# Crumb_Adapter_neu2V1_2.net
KiCad netlist of a schematic drawn in EAGLE
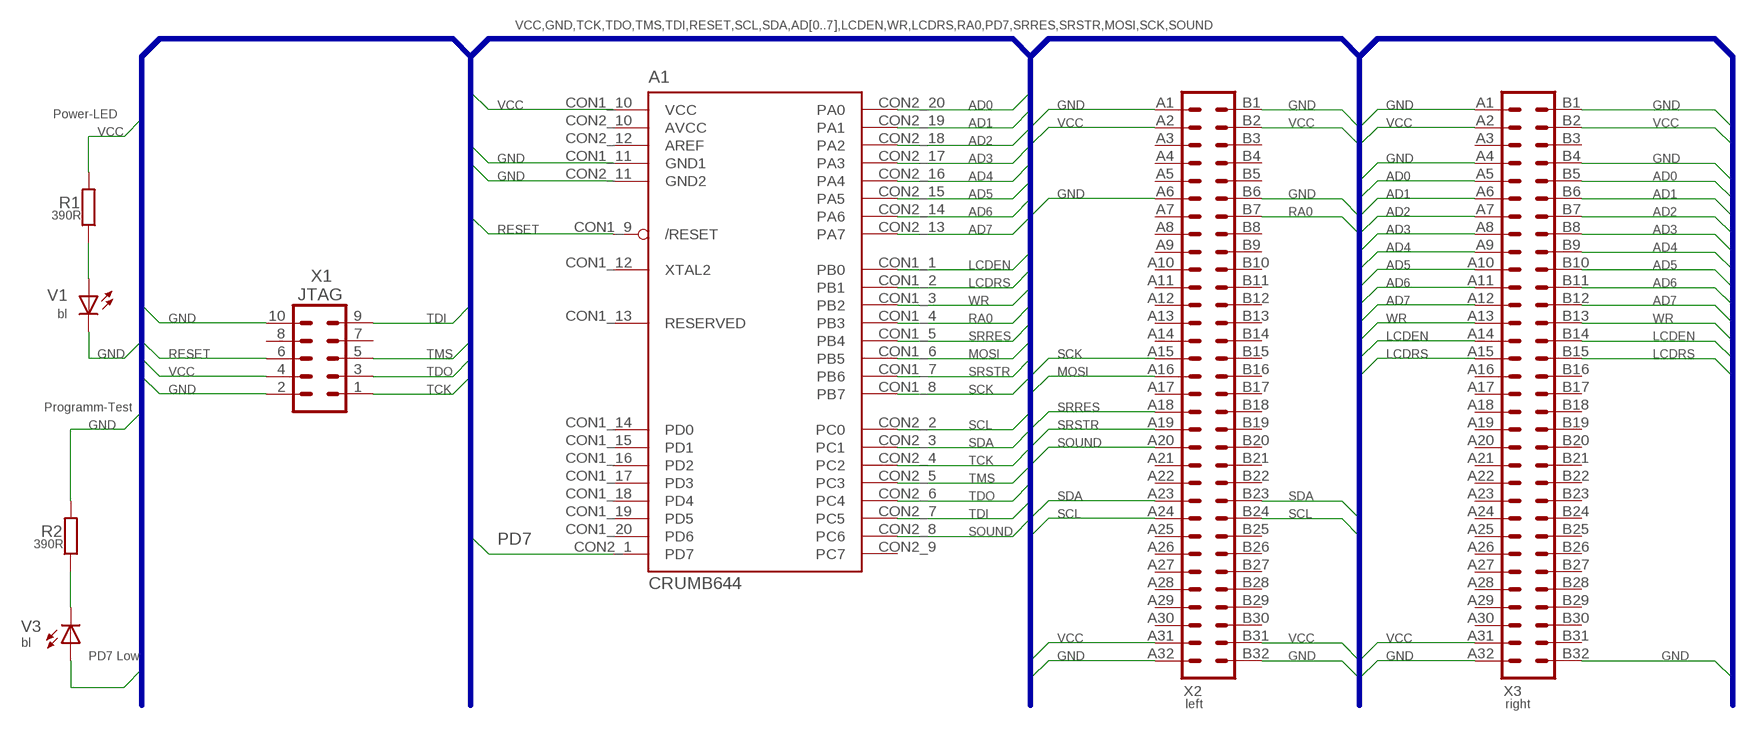
[diagram p0: schematic, sheet 1]

(export (version "E")
  (design (tool "Eeschema 10.0.6"))
  (components
    (comp (ref "A1")
      (value "CRUMB644")
      (footprint "eagle-import:CRUMB644")
      (libsource (lib "eagle-import") (part "CRUMB644"))
    )
    (comp (ref "R1")
      (value "390R")
      (footprint "eagle-import:M1206")
      (libsource (lib "eagle-import") (part "R-EU_VM1206"))
    )
    (comp (ref "R2")
      (value "390R")
      (footprint "eagle-import:M1206")
      (libsource (lib "eagle-import") (part "R-EU_VM1206"))
    )
    (comp (ref "V1")
      (value "bl")
      (footprint "eagle-import:CHIPLED_1206")
      (libsource (lib "eagle-import") (part "LEDCHIPLED_1206"))
    )
    (comp (ref "V3")
      (value "bl")
      (footprint "eagle-import:CHIPLED_1206")
      (libsource (lib "eagle-import") (part "LEDCHIPLED_1206"))
    )
    (comp (ref "X1")
      (value "JTAG")
      (footprint "eagle-import:MA05-2")
      (libsource (lib "eagle-import") (part "MA05-2"))
    )
    (comp (ref "X2")
      (value "left")
      (footprint "eagle-import:MAB32-2")
      (libsource (lib "eagle-import") (part "MAB64"))
    )
    (comp (ref "X3")
      (value "right")
      (footprint "eagle-import:MAB32-2")
      (libsource (lib "eagle-import") (part "MAB64"))
    )
  )
  (nets
    (net (code "1") (name "/AD0") (class "Default")
      (node (ref "A1") (pin "CON2_20") (pinfunction "PA0_CON2_20") (pintype "bidirectional"))
      (node (ref "X3") (pin "A5") (pinfunction "A5_A5") (pintype "passive"))
      (node (ref "X3") (pin "B5") (pinfunction "B5_B5") (pintype "passive"))
    )
    (net (code "2") (name "/AD1") (class "Default")
      (node (ref "A1") (pin "CON2_19") (pinfunction "PA1_CON2_19") (pintype "bidirectional"))
      (node (ref "X3") (pin "A6") (pinfunction "A6_A6") (pintype "passive"))
      (node (ref "X3") (pin "B6") (pinfunction "B6_B6") (pintype "passive"))
    )
    (net (code "3") (name "/AD2") (class "Default")
      (node (ref "A1") (pin "CON2_18") (pinfunction "PA2_CON2_18") (pintype "bidirectional"))
      (node (ref "X3") (pin "A7") (pinfunction "A7_A7") (pintype "passive"))
      (node (ref "X3") (pin "B7") (pinfunction "B7_B7") (pintype "passive"))
    )
    (net (code "4") (name "/AD3") (class "Default")
      (node (ref "A1") (pin "CON2_17") (pinfunction "PA3_CON2_17") (pintype "bidirectional"))
      (node (ref "X3") (pin "A8") (pinfunction "A8_A8") (pintype "passive"))
      (node (ref "X3") (pin "B8") (pinfunction "B8_B8") (pintype "passive"))
    )
    (net (code "5") (name "/AD4") (class "Default")
      (node (ref "A1") (pin "CON2_16") (pinfunction "PA4_CON2_16") (pintype "bidirectional"))
      (node (ref "X3") (pin "A9") (pinfunction "A9_A9") (pintype "passive"))
      (node (ref "X3") (pin "B9") (pinfunction "B9_B9") (pintype "passive"))
    )
    (net (code "6") (name "/AD5") (class "Default")
      (node (ref "A1") (pin "CON2_15") (pinfunction "PA5_CON2_15") (pintype "bidirectional"))
      (node (ref "X3") (pin "A10") (pinfunction "A10_A10") (pintype "passive"))
      (node (ref "X3") (pin "B10") (pinfunction "B10_B10") (pintype "passive"))
    )
    (net (code "7") (name "/AD6") (class "Default")
      (node (ref "A1") (pin "CON2_14") (pinfunction "PA6_CON2_14") (pintype "bidirectional"))
      (node (ref "X3") (pin "A11") (pinfunction "A11_A11") (pintype "passive"))
      (node (ref "X3") (pin "B11") (pinfunction "B11_B11") (pintype "passive"))
    )
    (net (code "8") (name "/AD7") (class "Default")
      (node (ref "A1") (pin "CON2_13") (pinfunction "PA7_CON2_13") (pintype "bidirectional"))
      (node (ref "X3") (pin "A12") (pinfunction "A12_A12") (pintype "passive"))
      (node (ref "X3") (pin "B12") (pinfunction "B12_B12") (pintype "passive"))
    )
    (net (code "9") (name "/GND") (class "Default")
      (node (ref "A1") (pin "CON1_11") (pinfunction "GND1_CON1_11") (pintype "power_in"))
      (node (ref "A1") (pin "CON2_11") (pinfunction "GND2_CON2_11") (pintype "power_in"))
      (node (ref "R2") (pin "2") (pinfunction "2_2") (pintype "passive"))
      (node (ref "V1") (pin "C") (pinfunction "C_C") (pintype "passive"))
      (node (ref "X1") (pin "10") (pinfunction "10_10") (pintype "passive"))
      (node (ref "X1") (pin "2") (pinfunction "2_2") (pintype "passive"))
      (node (ref "X2") (pin "A1") (pinfunction "A1_A1") (pintype "passive"))
      (node (ref "X2") (pin "A32") (pinfunction "A32_A32") (pintype "passive"))
      (node (ref "X2") (pin "A6") (pinfunction "A6_A6") (pintype "passive"))
      (node (ref "X2") (pin "B1") (pinfunction "B1_B1") (pintype "passive"))
      (node (ref "X2") (pin "B32") (pinfunction "B32_B32") (pintype "passive"))
      (node (ref "X2") (pin "B6") (pinfunction "B6_B6") (pintype "passive"))
      (node (ref "X3") (pin "A1") (pinfunction "A1_A1") (pintype "passive"))
      (node (ref "X3") (pin "A32") (pinfunction "A32_A32") (pintype "passive"))
      (node (ref "X3") (pin "A4") (pinfunction "A4_A4") (pintype "passive"))
      (node (ref "X3") (pin "B1") (pinfunction "B1_B1") (pintype "passive"))
      (node (ref "X3") (pin "B32") (pinfunction "B32_B32") (pintype "passive"))
      (node (ref "X3") (pin "B4") (pinfunction "B4_B4") (pintype "passive"))
    )
    (net (code "10") (name "/LCDEN") (class "Default")
      (node (ref "A1") (pin "CON1_1") (pinfunction "PB0_CON1_1") (pintype "bidirectional"))
      (node (ref "X3") (pin "A14") (pinfunction "A14_A14") (pintype "passive"))
      (node (ref "X3") (pin "B14") (pinfunction "B14_B14") (pintype "passive"))
    )
    (net (code "11") (name "/LCDRS") (class "Default")
      (node (ref "A1") (pin "CON1_2") (pinfunction "PB1_CON1_2") (pintype "bidirectional"))
      (node (ref "X3") (pin "A15") (pinfunction "A15_A15") (pintype "passive"))
      (node (ref "X3") (pin "B15") (pinfunction "B15_B15") (pintype "passive"))
    )
    (net (code "12") (name "/MOSI") (class "Default")
      (node (ref "A1") (pin "CON1_6") (pinfunction "PB5_CON1_6") (pintype "bidirectional"))
      (node (ref "X2") (pin "A16") (pinfunction "A16_A16") (pintype "passive"))
    )
    (net (code "13") (name "/PD7") (class "Default")
      (node (ref "A1") (pin "CON2_1") (pinfunction "PD7_CON2_1") (pintype "bidirectional"))
      (node (ref "V3") (pin "A") (pinfunction "A_A") (pintype "passive"))
    )
    (net (code "14") (name "/RA0") (class "Default")
      (node (ref "A1") (pin "CON1_4") (pinfunction "PB3_CON1_4") (pintype "bidirectional"))
      (node (ref "X2") (pin "B7") (pinfunction "B7_B7") (pintype "passive"))
    )
    (net (code "15") (name "/RESET") (class "Default")
      (node (ref "A1") (pin "CON1_9") (pinfunction "/RESET_CON1_9") (pintype "input"))
      (node (ref "X1") (pin "6") (pinfunction "6_6") (pintype "passive"))
    )
    (net (code "16") (name "/SCK") (class "Default")
      (node (ref "A1") (pin "CON1_8") (pinfunction "PB7_CON1_8") (pintype "bidirectional"))
      (node (ref "X2") (pin "A15") (pinfunction "A15_A15") (pintype "passive"))
    )
    (net (code "17") (name "/SCL") (class "Default")
      (node (ref "A1") (pin "CON2_2") (pinfunction "PC0_CON2_2") (pintype "bidirectional"))
      (node (ref "X2") (pin "A24") (pinfunction "A24_A24") (pintype "passive"))
      (node (ref "X2") (pin "B24") (pinfunction "B24_B24") (pintype "passive"))
    )
    (net (code "18") (name "/SDA") (class "Default")
      (node (ref "A1") (pin "CON2_3") (pinfunction "PC1_CON2_3") (pintype "bidirectional"))
      (node (ref "X2") (pin "A23") (pinfunction "A23_A23") (pintype "passive"))
      (node (ref "X2") (pin "B23") (pinfunction "B23_B23") (pintype "passive"))
    )
    (net (code "19") (name "/SOUND") (class "Default")
      (node (ref "A1") (pin "CON2_8") (pinfunction "PC6_CON2_8") (pintype "bidirectional"))
      (node (ref "X2") (pin "A20") (pinfunction "A20_A20") (pintype "passive"))
    )
    (net (code "20") (name "/SRRES") (class "Default")
      (node (ref "A1") (pin "CON1_5") (pinfunction "PB4_CON1_5") (pintype "bidirectional"))
      (node (ref "X2") (pin "A18") (pinfunction "A18_A18") (pintype "passive"))
    )
    (net (code "21") (name "/SRSTR") (class "Default")
      (node (ref "A1") (pin "CON1_7") (pinfunction "PB6_CON1_7") (pintype "bidirectional"))
      (node (ref "X2") (pin "A19") (pinfunction "A19_A19") (pintype "passive"))
    )
    (net (code "22") (name "/TCK") (class "Default")
      (node (ref "A1") (pin "CON2_4") (pinfunction "PC2_CON2_4") (pintype "bidirectional"))
      (node (ref "X1") (pin "1") (pinfunction "1_1") (pintype "passive"))
    )
    (net (code "23") (name "/TDI") (class "Default")
      (node (ref "A1") (pin "CON2_7") (pinfunction "PC5_CON2_7") (pintype "bidirectional"))
      (node (ref "X1") (pin "9") (pinfunction "9_9") (pintype "passive"))
    )
    (net (code "24") (name "/TDO") (class "Default")
      (node (ref "A1") (pin "CON2_6") (pinfunction "PC4_CON2_6") (pintype "bidirectional"))
      (node (ref "X1") (pin "3") (pinfunction "3_3") (pintype "passive"))
    )
    (net (code "25") (name "/TMS") (class "Default")
      (node (ref "A1") (pin "CON2_5") (pinfunction "PC3_CON2_5") (pintype "bidirectional"))
      (node (ref "X1") (pin "5") (pinfunction "5_5") (pintype "passive"))
    )
    (net (code "26") (name "/VCC") (class "Default")
      (node (ref "A1") (pin "CON1_10") (pinfunction "VCC_CON1_10") (pintype "power_in"))
      (node (ref "R1") (pin "2") (pinfunction "2_2") (pintype "passive"))
      (node (ref "X1") (pin "4") (pinfunction "4_4") (pintype "passive"))
      (node (ref "X2") (pin "A2") (pinfunction "A2_A2") (pintype "passive"))
      (node (ref "X2") (pin "A31") (pinfunction "A31_A31") (pintype "passive"))
      (node (ref "X2") (pin "B2") (pinfunction "B2_B2") (pintype "passive"))
      (node (ref "X2") (pin "B31") (pinfunction "B31_B31") (pintype "passive"))
      (node (ref "X3") (pin "A2") (pinfunction "A2_A2") (pintype "passive"))
      (node (ref "X3") (pin "A31") (pinfunction "A31_A31") (pintype "passive"))
      (node (ref "X3") (pin "B2") (pinfunction "B2_B2") (pintype "passive"))
    )
    (net (code "27") (name "/WR") (class "Default")
      (node (ref "A1") (pin "CON1_3") (pinfunction "PB2_CON1_3") (pintype "bidirectional"))
      (node (ref "X3") (pin "A13") (pinfunction "A13_A13") (pintype "passive"))
      (node (ref "X3") (pin "B13") (pinfunction "B13_B13") (pintype "passive"))
    )
    (net (code "29") (name "Net-(R1-Pad1)") (class "Default")
      (node (ref "R1") (pin "1") (pinfunction "1_1") (pintype "passive"))
      (node (ref "V1") (pin "A") (pinfunction "A_A") (pintype "passive"))
    )
    (net (code "30") (name "Net-(R2-Pad1)") (class "Default")
      (node (ref "R2") (pin "1") (pinfunction "1_1") (pintype "passive"))
      (node (ref "V3") (pin "C") (pinfunction "C_C") (pintype "passive"))
    )
    (net (code "31") (name "unconnected-(A1-AREF-PadCON2_12)") (class "Default")
      (node (ref "A1") (pin "CON2_12") (pinfunction "AREF_CON2_12") (pintype "input"))
    )
    (net (code "32") (name "unconnected-(A1-AVCC-PadCON2_10)") (class "Default")
      (node (ref "A1") (pin "CON2_10") (pinfunction "AVCC_CON2_10") (pintype "input"))
    )
    (net (code "33") (name "unconnected-(A1-PC7-PadCON2_9)") (class "Default")
      (node (ref "A1") (pin "CON2_9") (pinfunction "PC7_CON2_9") (pintype "bidirectional"))
    )
    (net (code "34") (name "unconnected-(A1-PD0-PadCON1_14)") (class "Default")
      (node (ref "A1") (pin "CON1_14") (pinfunction "PD0_CON1_14") (pintype "bidirectional"))
    )
    (net (code "35") (name "unconnected-(A1-PD1-PadCON1_15)") (class "Default")
      (node (ref "A1") (pin "CON1_15") (pinfunction "PD1_CON1_15") (pintype "bidirectional"))
    )
    (net (code "36") (name "unconnected-(A1-PD2-PadCON1_16)") (class "Default")
      (node (ref "A1") (pin "CON1_16") (pinfunction "PD2_CON1_16") (pintype "bidirectional"))
    )
    (net (code "37") (name "unconnected-(A1-PD3-PadCON1_17)") (class "Default")
      (node (ref "A1") (pin "CON1_17") (pinfunction "PD3_CON1_17") (pintype "bidirectional"))
    )
    (net (code "38") (name "unconnected-(A1-PD4-PadCON1_18)") (class "Default")
      (node (ref "A1") (pin "CON1_18") (pinfunction "PD4_CON1_18") (pintype "bidirectional"))
    )
    (net (code "39") (name "unconnected-(A1-PD5-PadCON1_19)") (class "Default")
      (node (ref "A1") (pin "CON1_19") (pinfunction "PD5_CON1_19") (pintype "bidirectional"))
    )
    (net (code "40") (name "unconnected-(A1-PD6-PadCON1_20)") (class "Default")
      (node (ref "A1") (pin "CON1_20") (pinfunction "PD6_CON1_20") (pintype "bidirectional"))
    )
    (net (code "41") (name "unconnected-(A1-RESERVED-PadCON1_13)") (class "Default")
      (node (ref "A1") (pin "CON1_13") (pinfunction "RESERVED_CON1_13") (pintype "no_connect"))
    )
    (net (code "42") (name "unconnected-(A1-XTAL2-PadCON1_12)") (class "Default")
      (node (ref "A1") (pin "CON1_12") (pinfunction "XTAL2_CON1_12") (pintype "bidirectional"))
    )
    (net (code "43") (name "unconnected-(X1-Pad7)") (class "Default")
      (node (ref "X1") (pin "7") (pinfunction "7_7") (pintype "passive"))
    )
    (net (code "44") (name "unconnected-(X1-Pad8)") (class "Default")
      (node (ref "X1") (pin "8") (pinfunction "8_8") (pintype "passive"))
    )
    (net (code "45") (name "unconnected-(X2-PadA3)") (class "Default")
      (node (ref "X2") (pin "A3") (pinfunction "A3_A3") (pintype "passive"))
    )
    (net (code "46") (name "unconnected-(X2-PadA4)") (class "Default")
      (node (ref "X2") (pin "A4") (pinfunction "A4_A4") (pintype "passive"))
    )
    (net (code "47") (name "unconnected-(X2-PadA5)") (class "Default")
      (node (ref "X2") (pin "A5") (pinfunction "A5_A5") (pintype "passive"))
    )
    (net (code "48") (name "unconnected-(X2-PadA7)") (class "Default")
      (node (ref "X2") (pin "A7") (pinfunction "A7_A7") (pintype "passive"))
    )
    (net (code "49") (name "unconnected-(X2-PadA8)") (class "Default")
      (node (ref "X2") (pin "A8") (pinfunction "A8_A8") (pintype "passive"))
    )
    (net (code "50") (name "unconnected-(X2-PadA9)") (class "Default")
      (node (ref "X2") (pin "A9") (pinfunction "A9_A9") (pintype "passive"))
    )
    (net (code "51") (name "unconnected-(X2-PadA10)") (class "Default")
      (node (ref "X2") (pin "A10") (pinfunction "A10_A10") (pintype "passive"))
    )
    (net (code "52") (name "unconnected-(X2-PadA11)") (class "Default")
      (node (ref "X2") (pin "A11") (pinfunction "A11_A11") (pintype "passive"))
    )
    (net (code "53") (name "unconnected-(X2-PadA12)") (class "Default")
      (node (ref "X2") (pin "A12") (pinfunction "A12_A12") (pintype "passive"))
    )
    (net (code "54") (name "unconnected-(X2-PadA13)") (class "Default")
      (node (ref "X2") (pin "A13") (pinfunction "A13_A13") (pintype "passive"))
    )
    (net (code "55") (name "unconnected-(X2-PadA14)") (class "Default")
      (node (ref "X2") (pin "A14") (pinfunction "A14_A14") (pintype "passive"))
    )
    (net (code "56") (name "unconnected-(X2-PadA17)") (class "Default")
      (node (ref "X2") (pin "A17") (pinfunction "A17_A17") (pintype "passive"))
    )
    (net (code "57") (name "unconnected-(X2-PadA21)") (class "Default")
      (node (ref "X2") (pin "A21") (pinfunction "A21_A21") (pintype "passive"))
    )
    (net (code "58") (name "unconnected-(X2-PadA22)") (class "Default")
      (node (ref "X2") (pin "A22") (pinfunction "A22_A22") (pintype "passive"))
    )
    (net (code "59") (name "unconnected-(X2-PadA25)") (class "Default")
      (node (ref "X2") (pin "A25") (pinfunction "A25_A25") (pintype "passive"))
    )
    (net (code "60") (name "unconnected-(X2-PadA26)") (class "Default")
      (node (ref "X2") (pin "A26") (pinfunction "A26_A26") (pintype "passive"))
    )
    (net (code "61") (name "unconnected-(X2-PadA27)") (class "Default")
      (node (ref "X2") (pin "A27") (pinfunction "A27_A27") (pintype "passive"))
    )
    (net (code "62") (name "unconnected-(X2-PadA28)") (class "Default")
      (node (ref "X2") (pin "A28") (pinfunction "A28_A28") (pintype "passive"))
    )
    (net (code "63") (name "unconnected-(X2-PadA29)") (class "Default")
      (node (ref "X2") (pin "A29") (pinfunction "A29_A29") (pintype "passive"))
    )
    (net (code "64") (name "unconnected-(X2-PadA30)") (class "Default")
      (node (ref "X2") (pin "A30") (pinfunction "A30_A30") (pintype "passive"))
    )
    (net (code "65") (name "unconnected-(X2-PadB3)") (class "Default")
      (node (ref "X2") (pin "B3") (pinfunction "B3_B3") (pintype "passive"))
    )
    (net (code "66") (name "unconnected-(X2-PadB4)") (class "Default")
      (node (ref "X2") (pin "B4") (pinfunction "B4_B4") (pintype "passive"))
    )
    (net (code "67") (name "unconnected-(X2-PadB5)") (class "Default")
      (node (ref "X2") (pin "B5") (pinfunction "B5_B5") (pintype "passive"))
    )
    (net (code "68") (name "unconnected-(X2-PadB8)") (class "Default")
      (node (ref "X2") (pin "B8") (pinfunction "B8_B8") (pintype "passive"))
    )
    (net (code "69") (name "unconnected-(X2-PadB9)") (class "Default")
      (node (ref "X2") (pin "B9") (pinfunction "B9_B9") (pintype "passive"))
    )
    (net (code "70") (name "unconnected-(X2-PadB10)") (class "Default")
      (node (ref "X2") (pin "B10") (pinfunction "B10_B10") (pintype "passive"))
    )
    (net (code "71") (name "unconnected-(X2-PadB11)") (class "Default")
      (node (ref "X2") (pin "B11") (pinfunction "B11_B11") (pintype "passive"))
    )
    (net (code "72") (name "unconnected-(X2-PadB12)") (class "Default")
      (node (ref "X2") (pin "B12") (pinfunction "B12_B12") (pintype "passive"))
    )
    (net (code "73") (name "unconnected-(X2-PadB13)") (class "Default")
      (node (ref "X2") (pin "B13") (pinfunction "B13_B13") (pintype "passive"))
    )
    (net (code "74") (name "unconnected-(X2-PadB14)") (class "Default")
      (node (ref "X2") (pin "B14") (pinfunction "B14_B14") (pintype "passive"))
    )
    (net (code "75") (name "unconnected-(X2-PadB15)") (class "Default")
      (node (ref "X2") (pin "B15") (pinfunction "B15_B15") (pintype "passive"))
    )
    (net (code "76") (name "unconnected-(X2-PadB16)") (class "Default")
      (node (ref "X2") (pin "B16") (pinfunction "B16_B16") (pintype "passive"))
    )
    (net (code "77") (name "unconnected-(X2-PadB17)") (class "Default")
      (node (ref "X2") (pin "B17") (pinfunction "B17_B17") (pintype "passive"))
    )
    (net (code "78") (name "unconnected-(X2-PadB18)") (class "Default")
      (node (ref "X2") (pin "B18") (pinfunction "B18_B18") (pintype "passive"))
    )
    (net (code "79") (name "unconnected-(X2-PadB19)") (class "Default")
      (node (ref "X2") (pin "B19") (pinfunction "B19_B19") (pintype "passive"))
    )
    (net (code "80") (name "unconnected-(X2-PadB20)") (class "Default")
      (node (ref "X2") (pin "B20") (pinfunction "B20_B20") (pintype "passive"))
    )
    (net (code "81") (name "unconnected-(X2-PadB21)") (class "Default")
      (node (ref "X2") (pin "B21") (pinfunction "B21_B21") (pintype "passive"))
    )
    (net (code "82") (name "unconnected-(X2-PadB22)") (class "Default")
      (node (ref "X2") (pin "B22") (pinfunction "B22_B22") (pintype "passive"))
    )
    (net (code "83") (name "unconnected-(X2-PadB25)") (class "Default")
      (node (ref "X2") (pin "B25") (pinfunction "B25_B25") (pintype "passive"))
    )
    (net (code "84") (name "unconnected-(X2-PadB26)") (class "Default")
      (node (ref "X2") (pin "B26") (pinfunction "B26_B26") (pintype "passive"))
    )
    (net (code "85") (name "unconnected-(X2-PadB27)") (class "Default")
      (node (ref "X2") (pin "B27") (pinfunction "B27_B27") (pintype "passive"))
    )
    (net (code "86") (name "unconnected-(X2-PadB28)") (class "Default")
      (node (ref "X2") (pin "B28") (pinfunction "B28_B28") (pintype "passive"))
    )
    (net (code "87") (name "unconnected-(X2-PadB29)") (class "Default")
      (node (ref "X2") (pin "B29") (pinfunction "B29_B29") (pintype "passive"))
    )
    (net (code "88") (name "unconnected-(X2-PadB30)") (class "Default")
      (node (ref "X2") (pin "B30") (pinfunction "B30_B30") (pintype "passive"))
    )
    (net (code "89") (name "unconnected-(X3-PadA3)") (class "Default")
      (node (ref "X3") (pin "A3") (pinfunction "A3_A3") (pintype "passive"))
    )
    (net (code "90") (name "unconnected-(X3-PadA16)") (class "Default")
      (node (ref "X3") (pin "A16") (pinfunction "A16_A16") (pintype "passive"))
    )
    (net (code "91") (name "unconnected-(X3-PadA17)") (class "Default")
      (node (ref "X3") (pin "A17") (pinfunction "A17_A17") (pintype "passive"))
    )
    (net (code "92") (name "unconnected-(X3-PadA18)") (class "Default")
      (node (ref "X3") (pin "A18") (pinfunction "A18_A18") (pintype "passive"))
    )
    (net (code "93") (name "unconnected-(X3-PadA19)") (class "Default")
      (node (ref "X3") (pin "A19") (pinfunction "A19_A19") (pintype "passive"))
    )
    (net (code "94") (name "unconnected-(X3-PadA20)") (class "Default")
      (node (ref "X3") (pin "A20") (pinfunction "A20_A20") (pintype "passive"))
    )
    (net (code "95") (name "unconnected-(X3-PadA21)") (class "Default")
      (node (ref "X3") (pin "A21") (pinfunction "A21_A21") (pintype "passive"))
    )
    (net (code "96") (name "unconnected-(X3-PadA22)") (class "Default")
      (node (ref "X3") (pin "A22") (pinfunction "A22_A22") (pintype "passive"))
    )
    (net (code "97") (name "unconnected-(X3-PadA23)") (class "Default")
      (node (ref "X3") (pin "A23") (pinfunction "A23_A23") (pintype "passive"))
    )
    (net (code "98") (name "unconnected-(X3-PadA24)") (class "Default")
      (node (ref "X3") (pin "A24") (pinfunction "A24_A24") (pintype "passive"))
    )
    (net (code "99") (name "unconnected-(X3-PadA25)") (class "Default")
      (node (ref "X3") (pin "A25") (pinfunction "A25_A25") (pintype "passive"))
    )
    (net (code "100") (name "unconnected-(X3-PadA26)") (class "Default")
      (node (ref "X3") (pin "A26") (pinfunction "A26_A26") (pintype "passive"))
    )
    (net (code "101") (name "unconnected-(X3-PadA27)") (class "Default")
      (node (ref "X3") (pin "A27") (pinfunction "A27_A27") (pintype "passive"))
    )
    (net (code "102") (name "unconnected-(X3-PadA28)") (class "Default")
      (node (ref "X3") (pin "A28") (pinfunction "A28_A28") (pintype "passive"))
    )
    (net (code "103") (name "unconnected-(X3-PadA29)") (class "Default")
      (node (ref "X3") (pin "A29") (pinfunction "A29_A29") (pintype "passive"))
    )
    (net (code "104") (name "unconnected-(X3-PadA30)") (class "Default")
      (node (ref "X3") (pin "A30") (pinfunction "A30_A30") (pintype "passive"))
    )
    (net (code "105") (name "unconnected-(X3-PadB3)") (class "Default")
      (node (ref "X3") (pin "B3") (pinfunction "B3_B3") (pintype "passive"))
    )
    (net (code "106") (name "unconnected-(X3-PadB16)") (class "Default")
      (node (ref "X3") (pin "B16") (pinfunction "B16_B16") (pintype "passive"))
    )
    (net (code "107") (name "unconnected-(X3-PadB17)") (class "Default")
      (node (ref "X3") (pin "B17") (pinfunction "B17_B17") (pintype "passive"))
    )
    (net (code "108") (name "unconnected-(X3-PadB18)") (class "Default")
      (node (ref "X3") (pin "B18") (pinfunction "B18_B18") (pintype "passive"))
    )
    (net (code "109") (name "unconnected-(X3-PadB19)") (class "Default")
      (node (ref "X3") (pin "B19") (pinfunction "B19_B19") (pintype "passive"))
    )
    (net (code "110") (name "unconnected-(X3-PadB20)") (class "Default")
      (node (ref "X3") (pin "B20") (pinfunction "B20_B20") (pintype "passive"))
    )
    (net (code "111") (name "unconnected-(X3-PadB21)") (class "Default")
      (node (ref "X3") (pin "B21") (pinfunction "B21_B21") (pintype "passive"))
    )
    (net (code "112") (name "unconnected-(X3-PadB22)") (class "Default")
      (node (ref "X3") (pin "B22") (pinfunction "B22_B22") (pintype "passive"))
    )
    (net (code "113") (name "unconnected-(X3-PadB23)") (class "Default")
      (node (ref "X3") (pin "B23") (pinfunction "B23_B23") (pintype "passive"))
    )
    (net (code "114") (name "unconnected-(X3-PadB24)") (class "Default")
      (node (ref "X3") (pin "B24") (pinfunction "B24_B24") (pintype "passive"))
    )
    (net (code "115") (name "unconnected-(X3-PadB25)") (class "Default")
      (node (ref "X3") (pin "B25") (pinfunction "B25_B25") (pintype "passive"))
    )
    (net (code "116") (name "unconnected-(X3-PadB26)") (class "Default")
      (node (ref "X3") (pin "B26") (pinfunction "B26_B26") (pintype "passive"))
    )
    (net (code "117") (name "unconnected-(X3-PadB27)") (class "Default")
      (node (ref "X3") (pin "B27") (pinfunction "B27_B27") (pintype "passive"))
    )
    (net (code "118") (name "unconnected-(X3-PadB28)") (class "Default")
      (node (ref "X3") (pin "B28") (pinfunction "B28_B28") (pintype "passive"))
    )
    (net (code "119") (name "unconnected-(X3-PadB29)") (class "Default")
      (node (ref "X3") (pin "B29") (pinfunction "B29_B29") (pintype "passive"))
    )
    (net (code "120") (name "unconnected-(X3-PadB30)") (class "Default")
      (node (ref "X3") (pin "B30") (pinfunction "B30_B30") (pintype "passive"))
    )
    (net (code "121") (name "unconnected-(X3-PadB31)") (class "Default")
      (node (ref "X3") (pin "B31") (pinfunction "B31_B31") (pintype "passive"))
    )
  )
)
